# ME6408_Central_CTRL.net
KiCad netlist of a schematic drawn in EAGLE
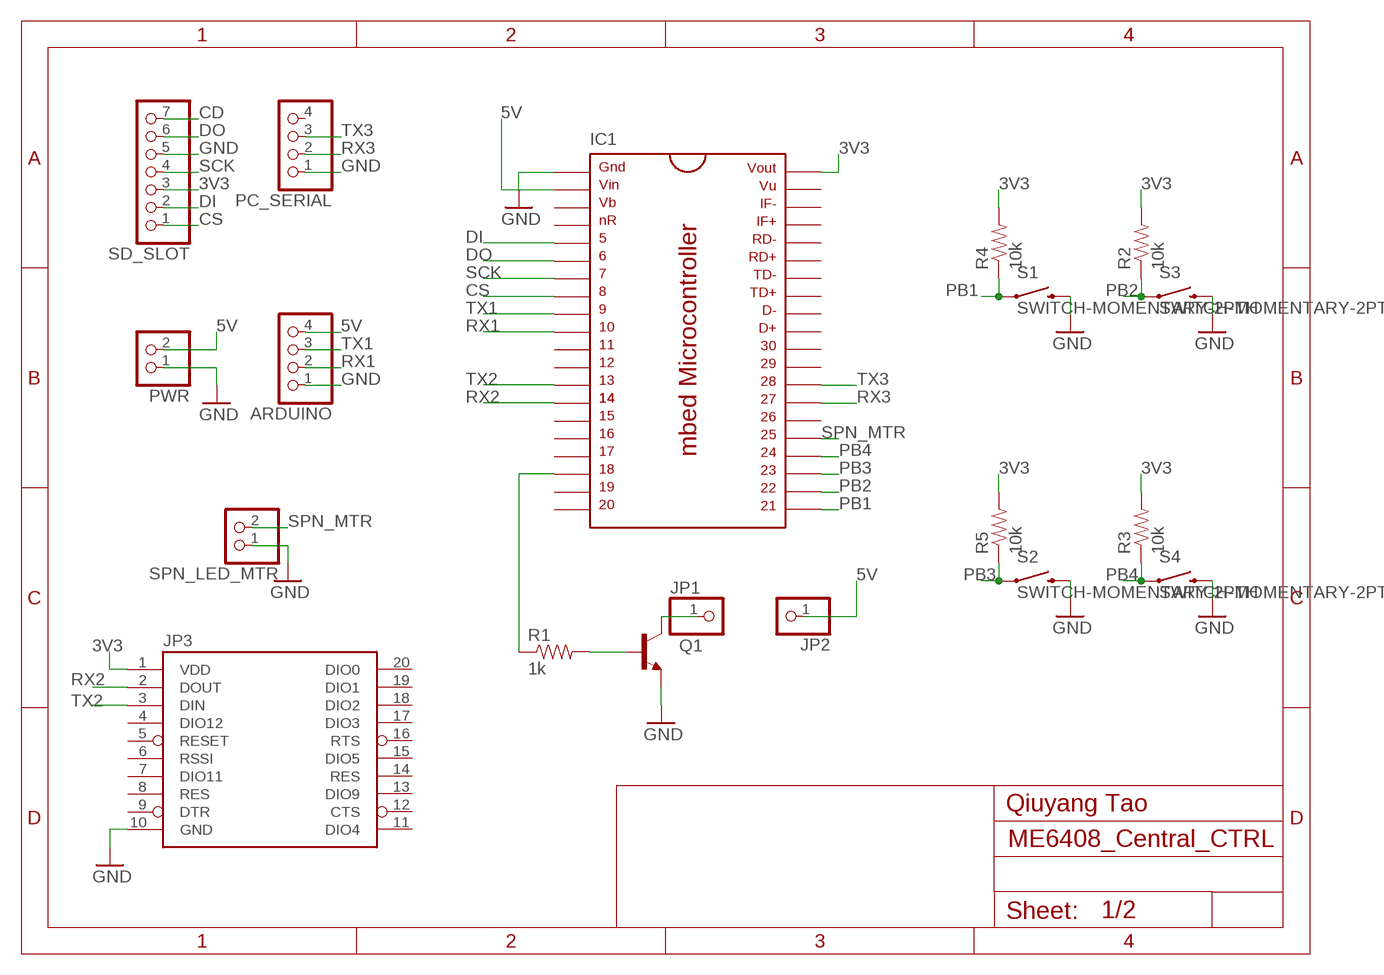
[diagram p0: schematic, sheet 1]

(export (version "E")
  (design (tool "Eeschema 10.0.6"))
  (components
    (comp (ref "ARDUINO")
      (value "PINHD-1X4")
      (footprint "eagle-import:1X04")
      (libsource (lib "eagle-import") (part "PINHD-1X4"))
    )
    (comp (ref "IC1")
      (value "MBED_MICROCONTROLLER")
      (footprint "eagle-import:DIL40_0.9")
      (libsource (lib "eagle-import") (part "MBED_MICROCONTROLLER"))
    )
    (comp (ref "JP1")
      (value "PINHD-1X1")
      (footprint "eagle-import:1X01")
      (libsource (lib "eagle-import") (part "PINHD-1X1"))
    )
    (comp (ref "JP2")
      (value "PINHD-1X1")
      (footprint "eagle-import:1X01")
      (libsource (lib "eagle-import") (part "PINHD-1X1"))
    )
    (comp (ref "JP3")
      (value "XBEE-1B1")
      (footprint "eagle-import:XBEE-1")
      (libsource (lib "eagle-import") (part "XBEE-1B1"))
    )
    (comp (ref "PC_SERIAL")
      (value "PINHD-1X4")
      (footprint "eagle-import:1X04")
      (libsource (lib "eagle-import") (part "PINHD-1X4"))
    )
    (comp (ref "PWR")
      (value "PINHD-1X2")
      (footprint "eagle-import:1X02")
      (libsource (lib "eagle-import") (part "PINHD-1X2"))
    )
    (comp (ref "Q1")
      (value "TRANSISTOR_NPNTO-92-AMMO")
      (footprint "eagle-import:TO-92-AMMO")
      (libsource (lib "eagle-import") (part "TRANSISTOR_NPNTO-92-AMMO"))
    )
    (comp (ref "R1")
      (value "1k")
      (footprint "eagle-import:AXIAL-0.3")
      (libsource (lib "eagle-import") (part "RESISTORAXIAL-0.3"))
    )
    (comp (ref "R2")
      (value "10k")
      (footprint "eagle-import:AXIAL-0.3")
      (libsource (lib "eagle-import") (part "RESISTORAXIAL-0.3"))
    )
    (comp (ref "R3")
      (value "10k")
      (footprint "eagle-import:AXIAL-0.3")
      (libsource (lib "eagle-import") (part "RESISTORAXIAL-0.3"))
    )
    (comp (ref "R4")
      (value "10k")
      (footprint "eagle-import:AXIAL-0.3")
      (libsource (lib "eagle-import") (part "RESISTORAXIAL-0.3"))
    )
    (comp (ref "R5")
      (value "10k")
      (footprint "eagle-import:AXIAL-0.3")
      (libsource (lib "eagle-import") (part "RESISTORAXIAL-0.3"))
    )
    (comp (ref "S1")
      (value "SWITCH-MOMENTARY-2PTH")
      (footprint "eagle-import:TACTILE-PTH")
      (libsource (lib "eagle-import") (part "SWITCH-MOMENTARY-2PTH"))
    )
    (comp (ref "S2")
      (value "SWITCH-MOMENTARY-2PTH")
      (footprint "eagle-import:TACTILE-PTH")
      (libsource (lib "eagle-import") (part "SWITCH-MOMENTARY-2PTH"))
    )
    (comp (ref "S3")
      (value "SWITCH-MOMENTARY-2PTH")
      (footprint "eagle-import:TACTILE-PTH")
      (libsource (lib "eagle-import") (part "SWITCH-MOMENTARY-2PTH"))
    )
    (comp (ref "S4")
      (value "SWITCH-MOMENTARY-2PTH")
      (footprint "eagle-import:TACTILE-PTH")
      (libsource (lib "eagle-import") (part "SWITCH-MOMENTARY-2PTH"))
    )
    (comp (ref "SD_SLOT")
      (value "PINHD-1X7")
      (footprint "eagle-import:1X07")
      (libsource (lib "eagle-import") (part "PINHD-1X7"))
    )
    (comp (ref "SPN_LED_MTR")
      (value "PINHD-1X2")
      (footprint "eagle-import:1X02")
      (libsource (lib "eagle-import") (part "PINHD-1X2"))
    )
  )
  (nets
    (net (code "1") (name "3V3") (class "Default")
      (node (ref "IC1") (pin "40") (pinfunction "P$40_40") (pintype "bidirectional"))
      (node (ref "JP3") (pin "1") (pinfunction "VDD_1") (pintype "power_in"))
      (node (ref "R2") (pin "P$2") (pinfunction "2_P$2") (pintype "passive"))
      (node (ref "R3") (pin "P$2") (pinfunction "2_P$2") (pintype "passive"))
      (node (ref "R4") (pin "P$2") (pinfunction "2_P$2") (pintype "passive"))
      (node (ref "R5") (pin "P$2") (pinfunction "2_P$2") (pintype "passive"))
      (node (ref "SD_SLOT") (pin "3") (pinfunction "3_3") (pintype "passive"))
    )
    (net (code "2") (name "5V") (class "Default")
      (node (ref "ARDUINO") (pin "4") (pinfunction "4_4") (pintype "passive"))
      (node (ref "IC1") (pin "2") (pinfunction "P$2_2") (pintype "bidirectional"))
      (node (ref "JP2") (pin "1") (pinfunction "1_1") (pintype "passive"))
      (node (ref "PWR") (pin "2") (pinfunction "2_2") (pintype "passive"))
    )
    (net (code "3") (name "CD") (class "Default")
      (node (ref "SD_SLOT") (pin "7") (pinfunction "7_7") (pintype "passive"))
    )
    (net (code "4") (name "CS") (class "Default")
      (node (ref "IC1") (pin "8") (pinfunction "P$8_8") (pintype "bidirectional"))
      (node (ref "SD_SLOT") (pin "1") (pinfunction "1_1") (pintype "passive"))
    )
    (net (code "5") (name "DI") (class "Default")
      (node (ref "IC1") (pin "5") (pinfunction "P$5_5") (pintype "bidirectional"))
      (node (ref "SD_SLOT") (pin "2") (pinfunction "2_2") (pintype "passive"))
    )
    (net (code "6") (name "DO") (class "Default")
      (node (ref "IC1") (pin "6") (pinfunction "P$6_6") (pintype "bidirectional"))
      (node (ref "SD_SLOT") (pin "6") (pinfunction "6_6") (pintype "passive"))
    )
    (net (code "7") (name "GND") (class "Default")
      (node (ref "ARDUINO") (pin "1") (pinfunction "1_1") (pintype "passive"))
      (node (ref "IC1") (pin "1") (pinfunction "P$1_1") (pintype "bidirectional"))
      (node (ref "JP3") (pin "10") (pinfunction "GND_10") (pintype "power_in"))
      (node (ref "PC_SERIAL") (pin "1") (pinfunction "1_1") (pintype "passive"))
      (node (ref "PWR") (pin "1") (pinfunction "1_1") (pintype "passive"))
      (node (ref "Q1") (pin "1") (pinfunction "E_1") (pintype "passive"))
      (node (ref "S1") (pin "3") (pinfunction "2_3") (pintype "passive"))
      (node (ref "S2") (pin "3") (pinfunction "2_3") (pintype "passive"))
      (node (ref "S3") (pin "3") (pinfunction "2_3") (pintype "passive"))
      (node (ref "S4") (pin "3") (pinfunction "2_3") (pintype "passive"))
      (node (ref "SD_SLOT") (pin "5") (pinfunction "5_5") (pintype "passive"))
      (node (ref "SPN_LED_MTR") (pin "1") (pinfunction "1_1") (pintype "passive"))
    )
    (net (code "8") (name "Net-(IC1-P$18)") (class "Default")
      (node (ref "IC1") (pin "18") (pinfunction "P$18_18") (pintype "bidirectional"))
      (node (ref "R1") (pin "P$1") (pinfunction "1_P$1") (pintype "passive"))
    )
    (net (code "9") (name "Net-(Q1-B)") (class "Default")
      (node (ref "Q1") (pin "2") (pinfunction "B_2") (pintype "passive"))
      (node (ref "R1") (pin "P$2") (pinfunction "2_P$2") (pintype "passive"))
    )
    (net (code "10") (name "Net-(Q1-C)") (class "Default")
      (node (ref "JP1") (pin "1") (pinfunction "1_1") (pintype "passive"))
      (node (ref "Q1") (pin "3") (pinfunction "C_3") (pintype "passive"))
    )
    (net (code "11") (name "PB1") (class "Default")
      (node (ref "IC1") (pin "21") (pinfunction "P$21_21") (pintype "bidirectional"))
      (node (ref "R4") (pin "P$1") (pinfunction "1_P$1") (pintype "passive"))
      (node (ref "S1") (pin "1") (pinfunction "1_1") (pintype "passive"))
    )
    (net (code "12") (name "PB2") (class "Default")
      (node (ref "IC1") (pin "22") (pinfunction "P$22_22") (pintype "bidirectional"))
      (node (ref "R2") (pin "P$1") (pinfunction "1_P$1") (pintype "passive"))
      (node (ref "S3") (pin "1") (pinfunction "1_1") (pintype "passive"))
    )
    (net (code "13") (name "PB3") (class "Default")
      (node (ref "IC1") (pin "23") (pinfunction "P$23_23") (pintype "bidirectional"))
      (node (ref "R5") (pin "P$1") (pinfunction "1_P$1") (pintype "passive"))
      (node (ref "S2") (pin "1") (pinfunction "1_1") (pintype "passive"))
    )
    (net (code "14") (name "PB4") (class "Default")
      (node (ref "IC1") (pin "24") (pinfunction "P$24_24") (pintype "bidirectional"))
      (node (ref "R3") (pin "P$1") (pinfunction "1_P$1") (pintype "passive"))
      (node (ref "S4") (pin "1") (pinfunction "1_1") (pintype "passive"))
    )
    (net (code "15") (name "RX1") (class "Default")
      (node (ref "ARDUINO") (pin "2") (pinfunction "2_2") (pintype "passive"))
      (node (ref "IC1") (pin "10") (pinfunction "P$10_10") (pintype "bidirectional"))
    )
    (net (code "16") (name "RX2") (class "Default")
      (node (ref "IC1") (pin "14") (pinfunction "P$14_14") (pintype "bidirectional"))
      (node (ref "JP3") (pin "2") (pinfunction "DOUT_2") (pintype "output"))
    )
    (net (code "17") (name "RX3") (class "Default")
      (node (ref "IC1") (pin "27") (pinfunction "P$27_27") (pintype "bidirectional"))
      (node (ref "PC_SERIAL") (pin "2") (pinfunction "2_2") (pintype "passive"))
    )
    (net (code "18") (name "SCK") (class "Default")
      (node (ref "IC1") (pin "7") (pinfunction "P$7_7") (pintype "bidirectional"))
      (node (ref "SD_SLOT") (pin "4") (pinfunction "4_4") (pintype "passive"))
    )
    (net (code "19") (name "SPN_MTR") (class "Default")
      (node (ref "IC1") (pin "25") (pinfunction "P$25_25") (pintype "bidirectional"))
      (node (ref "SPN_LED_MTR") (pin "2") (pinfunction "2_2") (pintype "passive"))
    )
    (net (code "20") (name "TX1") (class "Default")
      (node (ref "ARDUINO") (pin "3") (pinfunction "3_3") (pintype "passive"))
      (node (ref "IC1") (pin "9") (pinfunction "P$9_9") (pintype "bidirectional"))
    )
    (net (code "21") (name "TX2") (class "Default")
      (node (ref "IC1") (pin "13") (pinfunction "P$13_13") (pintype "bidirectional"))
      (node (ref "JP3") (pin "3") (pinfunction "DIN_3") (pintype "input"))
    )
    (net (code "22") (name "TX3") (class "Default")
      (node (ref "IC1") (pin "28") (pinfunction "P$28_28") (pintype "bidirectional"))
      (node (ref "PC_SERIAL") (pin "3") (pinfunction "3_3") (pintype "passive"))
    )
    (net (code "23") (name "unconnected-(IC1-P$3-Pad3)") (class "Default")
      (node (ref "IC1") (pin "3") (pinfunction "P$3_3") (pintype "bidirectional"))
    )
    (net (code "24") (name "unconnected-(IC1-P$4-Pad4)") (class "Default")
      (node (ref "IC1") (pin "4") (pinfunction "P$4_4") (pintype "bidirectional"))
    )
    (net (code "25") (name "unconnected-(IC1-P$11-Pad11)") (class "Default")
      (node (ref "IC1") (pin "11") (pinfunction "P$11_11") (pintype "bidirectional"))
    )
    (net (code "26") (name "unconnected-(IC1-P$12-Pad12)") (class "Default")
      (node (ref "IC1") (pin "12") (pinfunction "P$12_12") (pintype "bidirectional"))
    )
    (net (code "27") (name "unconnected-(IC1-P$15-Pad15)") (class "Default")
      (node (ref "IC1") (pin "15") (pinfunction "P$15_15") (pintype "bidirectional"))
    )
    (net (code "28") (name "unconnected-(IC1-P$16-Pad16)") (class "Default")
      (node (ref "IC1") (pin "16") (pinfunction "P$16_16") (pintype "bidirectional"))
    )
    (net (code "29") (name "unconnected-(IC1-P$17-Pad17)") (class "Default")
      (node (ref "IC1") (pin "17") (pinfunction "P$17_17") (pintype "bidirectional"))
    )
    (net (code "30") (name "unconnected-(IC1-P$19-Pad19)") (class "Default")
      (node (ref "IC1") (pin "19") (pinfunction "P$19_19") (pintype "bidirectional"))
    )
    (net (code "31") (name "unconnected-(IC1-P$20-Pad20)") (class "Default")
      (node (ref "IC1") (pin "20") (pinfunction "P$20_20") (pintype "bidirectional"))
    )
    (net (code "32") (name "unconnected-(IC1-P$26-Pad26)") (class "Default")
      (node (ref "IC1") (pin "26") (pinfunction "P$26_26") (pintype "bidirectional"))
    )
    (net (code "33") (name "unconnected-(IC1-P$29-Pad29)") (class "Default")
      (node (ref "IC1") (pin "29") (pinfunction "P$29_29") (pintype "bidirectional"))
    )
    (net (code "34") (name "unconnected-(IC1-P$30-Pad30)") (class "Default")
      (node (ref "IC1") (pin "30") (pinfunction "P$30_30") (pintype "bidirectional"))
    )
    (net (code "35") (name "unconnected-(IC1-P$31-Pad31)") (class "Default")
      (node (ref "IC1") (pin "31") (pinfunction "P$31_31") (pintype "bidirectional"))
    )
    (net (code "36") (name "unconnected-(IC1-P$32-Pad32)") (class "Default")
      (node (ref "IC1") (pin "32") (pinfunction "P$32_32") (pintype "bidirectional"))
    )
    (net (code "37") (name "unconnected-(IC1-P$33-Pad33)") (class "Default")
      (node (ref "IC1") (pin "33") (pinfunction "P$33_33") (pintype "bidirectional"))
    )
    (net (code "38") (name "unconnected-(IC1-P$34-Pad34)") (class "Default")
      (node (ref "IC1") (pin "34") (pinfunction "P$34_34") (pintype "bidirectional"))
    )
    (net (code "39") (name "unconnected-(IC1-P$35-Pad35)") (class "Default")
      (node (ref "IC1") (pin "35") (pinfunction "P$35_35") (pintype "bidirectional"))
    )
    (net (code "40") (name "unconnected-(IC1-P$36-Pad36)") (class "Default")
      (node (ref "IC1") (pin "36") (pinfunction "P$36_36") (pintype "bidirectional"))
    )
    (net (code "41") (name "unconnected-(IC1-P$37-Pad37)") (class "Default")
      (node (ref "IC1") (pin "37") (pinfunction "P$37_37") (pintype "bidirectional"))
    )
    (net (code "42") (name "unconnected-(IC1-P$38-Pad38)") (class "Default")
      (node (ref "IC1") (pin "38") (pinfunction "P$38_38") (pintype "bidirectional"))
    )
    (net (code "43") (name "unconnected-(IC1-P$39-Pad39)") (class "Default")
      (node (ref "IC1") (pin "39") (pinfunction "P$39_39") (pintype "bidirectional"))
    )
    (net (code "44") (name "unconnected-(JP3-CTS-Pad12)") (class "Default")
      (node (ref "JP3") (pin "12") (pinfunction "CTS_12") (pintype "output"))
    )
    (net (code "45") (name "unconnected-(JP3-DIO0-Pad20)") (class "Default")
      (node (ref "JP3") (pin "20") (pinfunction "DIO0_20") (pintype "bidirectional"))
    )
    (net (code "46") (name "unconnected-(JP3-DIO1-Pad19)") (class "Default")
      (node (ref "JP3") (pin "19") (pinfunction "DIO1_19") (pintype "bidirectional"))
    )
    (net (code "47") (name "unconnected-(JP3-DIO2-Pad18)") (class "Default")
      (node (ref "JP3") (pin "18") (pinfunction "DIO2_18") (pintype "bidirectional"))
    )
    (net (code "48") (name "unconnected-(JP3-DIO3-Pad17)") (class "Default")
      (node (ref "JP3") (pin "17") (pinfunction "DIO3_17") (pintype "bidirectional"))
    )
    (net (code "49") (name "unconnected-(JP3-DIO4-Pad11)") (class "Default")
      (node (ref "JP3") (pin "11") (pinfunction "DIO4_11") (pintype "bidirectional"))
    )
    (net (code "50") (name "unconnected-(JP3-DIO5-Pad15)") (class "Default")
      (node (ref "JP3") (pin "15") (pinfunction "DIO5_15") (pintype "bidirectional"))
    )
    (net (code "51") (name "unconnected-(JP3-DIO9-Pad13)") (class "Default")
      (node (ref "JP3") (pin "13") (pinfunction "DIO9_13") (pintype "bidirectional"))
    )
    (net (code "52") (name "unconnected-(JP3-DIO11-Pad7)") (class "Default")
      (node (ref "JP3") (pin "7") (pinfunction "DIO11_7") (pintype "bidirectional"))
    )
    (net (code "53") (name "unconnected-(JP3-DIO12-Pad4)") (class "Default")
      (node (ref "JP3") (pin "4") (pinfunction "DIO12_4") (pintype "bidirectional"))
    )
    (net (code "54") (name "unconnected-(JP3-DTR-Pad9)") (class "Default")
      (node (ref "JP3") (pin "9") (pinfunction "DTR_9") (pintype "bidirectional"))
    )
    (net (code "55") (name "unconnected-(JP3-RES-Pad8)") (class "Default")
      (node (ref "JP3") (pin "8") (pinfunction "RES_8") (pintype "bidirectional"))
    )
    (net (code "56") (name "unconnected-(JP3-RES-Pad14)") (class "Default")
      (node (ref "JP3") (pin "14") (pinfunction "RES_14") (pintype "bidirectional"))
    )
    (net (code "57") (name "unconnected-(JP3-RESET-Pad5)") (class "Default")
      (node (ref "JP3") (pin "5") (pinfunction "RESET_5") (pintype "input"))
    )
    (net (code "58") (name "unconnected-(JP3-RSSI-Pad6)") (class "Default")
      (node (ref "JP3") (pin "6") (pinfunction "RSSI_6") (pintype "bidirectional"))
    )
    (net (code "59") (name "unconnected-(JP3-RTS-Pad16)") (class "Default")
      (node (ref "JP3") (pin "16") (pinfunction "RTS_16") (pintype "input"))
    )
    (net (code "60") (name "unconnected-(PC_SERIAL-Pad4)") (class "Default")
      (node (ref "PC_SERIAL") (pin "4") (pinfunction "4_4") (pintype "passive"))
    )
  )
)
